# levelshifter.net
KiCad netlist of a schematic drawn in EAGLE
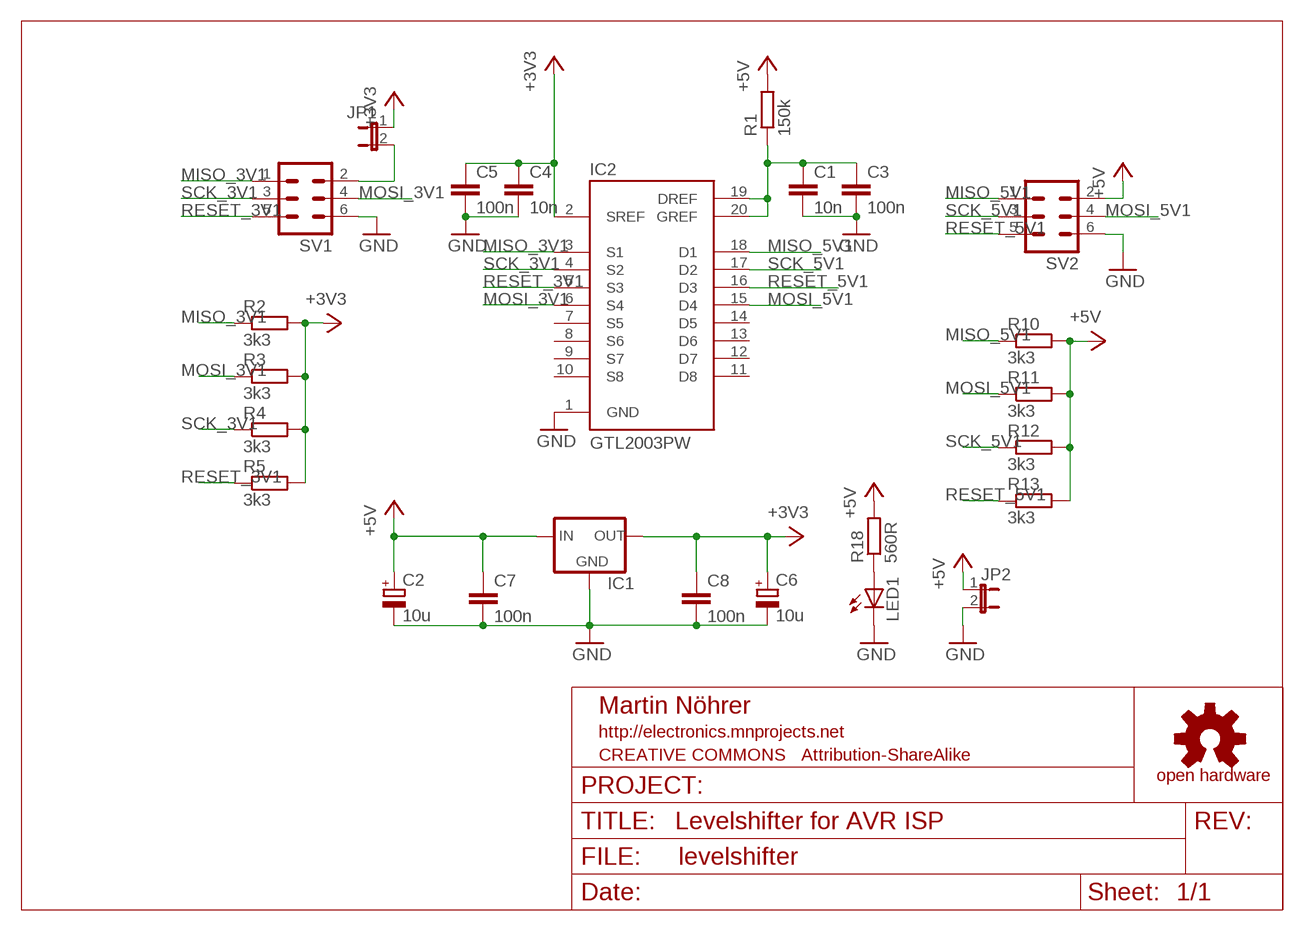
[diagram p0: schematic, sheet 1]

(export (version "E")
  (design (tool "Eeschema 10.0.6"))
  (components
    (comp (ref "C1")
      (value "10n")
      (footprint "eagle-import:C1206")
      (libsource (lib "eagle-import") (part "C-EUC1206"))
    )
    (comp (ref "C2")
      (value "10u")
      (footprint "eagle-import:SMC_C")
      (libsource (lib "eagle-import") (part "CPOL-EUSMCC"))
    )
    (comp (ref "C3")
      (value "100n")
      (footprint "eagle-import:C1206")
      (libsource (lib "eagle-import") (part "C-EUC1206"))
    )
    (comp (ref "C4")
      (value "10n")
      (footprint "eagle-import:C1206")
      (libsource (lib "eagle-import") (part "C-EUC1206"))
    )
    (comp (ref "C5")
      (value "100n")
      (footprint "eagle-import:C1206")
      (libsource (lib "eagle-import") (part "C-EUC1206"))
    )
    (comp (ref "C6")
      (value "10u")
      (footprint "eagle-import:SMC_C")
      (libsource (lib "eagle-import") (part "CPOL-EUSMCC"))
    )
    (comp (ref "C7")
      (value "100n")
      (footprint "eagle-import:C1206")
      (libsource (lib "eagle-import") (part "C-EUC1206"))
    )
    (comp (ref "C8")
      (value "100n")
      (footprint "eagle-import:C1206")
      (libsource (lib "eagle-import") (part "C-EUC1206"))
    )
    (comp (ref "IC1")
      (value "LM1117")
      (footprint "eagle-import:SOT223")
      (libsource (lib "eagle-import") (part "LM1117"))
    )
    (comp (ref "IC2")
      (value "GTL2003PW")
      (footprint "eagle-import:TSSOP20")
      (libsource (lib "eagle-import") (part "GTL2003PW"))
    )
    (comp (ref "JP1")
      (value "JP1E")
      (footprint "eagle-import:JP1")
      (libsource (lib "eagle-import") (part "JP1E"))
    )
    (comp (ref "JP2")
      (value "JP1E")
      (footprint "eagle-import:JP1")
      (libsource (lib "eagle-import") (part "JP1E"))
    )
    (comp (ref "LED1")
      (value "LEDSMT1206")
      (footprint "eagle-import:1206")
      (libsource (lib "eagle-import") (part "LEDSMT1206"))
    )
    (comp (ref "R1")
      (value "150k")
      (footprint "eagle-import:R1206")
      (libsource (lib "eagle-import") (part "R-EU_R1206"))
    )
    (comp (ref "R2")
      (value "3k3")
      (footprint "eagle-import:R1206")
      (libsource (lib "eagle-import") (part "R-EU_R1206"))
    )
    (comp (ref "R3")
      (value "3k3")
      (footprint "eagle-import:R1206")
      (libsource (lib "eagle-import") (part "R-EU_R1206"))
    )
    (comp (ref "R4")
      (value "3k3")
      (footprint "eagle-import:R1206")
      (libsource (lib "eagle-import") (part "R-EU_R1206"))
    )
    (comp (ref "R5")
      (value "3k3")
      (footprint "eagle-import:R1206")
      (libsource (lib "eagle-import") (part "R-EU_R1206"))
    )
    (comp (ref "R10")
      (value "3k3")
      (footprint "eagle-import:R1206")
      (libsource (lib "eagle-import") (part "R-EU_R1206"))
    )
    (comp (ref "R11")
      (value "3k3")
      (footprint "eagle-import:R1206")
      (libsource (lib "eagle-import") (part "R-EU_R1206"))
    )
    (comp (ref "R12")
      (value "3k3")
      (footprint "eagle-import:R1206")
      (libsource (lib "eagle-import") (part "R-EU_R1206"))
    )
    (comp (ref "R13")
      (value "3k3")
      (footprint "eagle-import:R1206")
      (libsource (lib "eagle-import") (part "R-EU_R1206"))
    )
    (comp (ref "R18")
      (value "560R")
      (footprint "eagle-import:R1206")
      (libsource (lib "eagle-import") (part "R-EU_R1206"))
    )
    (comp (ref "SV1")
      (value "ML6")
      (footprint "eagle-import:ML6")
      (libsource (lib "eagle-import") (part "ML6"))
    )
    (comp (ref "SV2")
      (value "ML6")
      (footprint "eagle-import:ML6")
      (libsource (lib "eagle-import") (part "ML6"))
    )
  )
  (nets
    (net (code "1") (name "+3V3") (class "Default")
      (node (ref "C4") (pin "1") (pinfunction "1_1") (pintype "passive"))
      (node (ref "C5") (pin "1") (pinfunction "1_1") (pintype "passive"))
      (node (ref "C6") (pin "+") (pinfunction "+_+") (pintype "passive"))
      (node (ref "C8") (pin "1") (pinfunction "1_1") (pintype "passive"))
      (node (ref "IC1") (pin "2") (pinfunction "OUT_2") (pintype "passive"))
      (node (ref "IC2") (pin "2") (pinfunction "SREF_2") (pintype "bidirectional"))
      (node (ref "JP1") (pin "1") (pinfunction "1_1") (pintype "passive"))
      (node (ref "R2") (pin "2") (pinfunction "2_2") (pintype "passive"))
      (node (ref "R3") (pin "2") (pinfunction "2_2") (pintype "passive"))
      (node (ref "R4") (pin "2") (pinfunction "2_2") (pintype "passive"))
      (node (ref "R5") (pin "2") (pinfunction "2_2") (pintype "passive"))
    )
    (net (code "2") (name "+5V") (class "Default")
      (node (ref "C2") (pin "+") (pinfunction "+_+") (pintype "passive"))
      (node (ref "C7") (pin "1") (pinfunction "1_1") (pintype "passive"))
      (node (ref "IC1") (pin "3") (pinfunction "IN_3") (pintype "input"))
      (node (ref "JP2") (pin "1") (pinfunction "1_1") (pintype "passive"))
      (node (ref "R1") (pin "2") (pinfunction "2_2") (pintype "passive"))
      (node (ref "R10") (pin "2") (pinfunction "2_2") (pintype "passive"))
      (node (ref "R11") (pin "2") (pinfunction "2_2") (pintype "passive"))
      (node (ref "R12") (pin "2") (pinfunction "2_2") (pintype "passive"))
      (node (ref "R13") (pin "2") (pinfunction "2_2") (pintype "passive"))
      (node (ref "R18") (pin "2") (pinfunction "2_2") (pintype "passive"))
      (node (ref "SV2") (pin "2") (pinfunction "2_2") (pintype "passive"))
    )
    (net (code "3") (name "/MISO_3V1") (class "Default")
      (node (ref "IC2") (pin "3") (pinfunction "S1_3") (pintype "bidirectional"))
      (node (ref "R2") (pin "1") (pinfunction "1_1") (pintype "passive"))
      (node (ref "SV1") (pin "1") (pinfunction "1_1") (pintype "passive"))
    )
    (net (code "4") (name "/MISO_5V1") (class "Default")
      (node (ref "IC2") (pin "18") (pinfunction "D1_18") (pintype "bidirectional"))
      (node (ref "R10") (pin "1") (pinfunction "1_1") (pintype "passive"))
      (node (ref "SV2") (pin "1") (pinfunction "1_1") (pintype "passive"))
    )
    (net (code "5") (name "/MOSI_3V1") (class "Default")
      (node (ref "IC2") (pin "6") (pinfunction "S4_6") (pintype "bidirectional"))
      (node (ref "R3") (pin "1") (pinfunction "1_1") (pintype "passive"))
      (node (ref "SV1") (pin "4") (pinfunction "4_4") (pintype "passive"))
    )
    (net (code "6") (name "/MOSI_5V1") (class "Default")
      (node (ref "IC2") (pin "15") (pinfunction "D4_15") (pintype "bidirectional"))
      (node (ref "R11") (pin "1") (pinfunction "1_1") (pintype "passive"))
      (node (ref "SV2") (pin "4") (pinfunction "4_4") (pintype "passive"))
    )
    (net (code "7") (name "/RESET_3V1") (class "Default")
      (node (ref "IC2") (pin "5") (pinfunction "S3_5") (pintype "bidirectional"))
      (node (ref "R5") (pin "1") (pinfunction "1_1") (pintype "passive"))
      (node (ref "SV1") (pin "5") (pinfunction "5_5") (pintype "passive"))
    )
    (net (code "8") (name "/RESET_5V1") (class "Default")
      (node (ref "IC2") (pin "16") (pinfunction "D3_16") (pintype "bidirectional"))
      (node (ref "R13") (pin "1") (pinfunction "1_1") (pintype "passive"))
      (node (ref "SV2") (pin "5") (pinfunction "5_5") (pintype "passive"))
    )
    (net (code "9") (name "/SCK_3V1") (class "Default")
      (node (ref "IC2") (pin "4") (pinfunction "S2_4") (pintype "bidirectional"))
      (node (ref "R4") (pin "1") (pinfunction "1_1") (pintype "passive"))
      (node (ref "SV1") (pin "3") (pinfunction "3_3") (pintype "passive"))
    )
    (net (code "10") (name "/SCK_5V1") (class "Default")
      (node (ref "IC2") (pin "17") (pinfunction "D2_17") (pintype "bidirectional"))
      (node (ref "R12") (pin "1") (pinfunction "1_1") (pintype "passive"))
      (node (ref "SV2") (pin "3") (pinfunction "3_3") (pintype "passive"))
    )
    (net (code "11") (name "GND") (class "Default")
      (node (ref "C1") (pin "2") (pinfunction "2_2") (pintype "passive"))
      (node (ref "C2") (pin "-") (pinfunction "-_-") (pintype "passive"))
      (node (ref "C3") (pin "2") (pinfunction "2_2") (pintype "passive"))
      (node (ref "C4") (pin "2") (pinfunction "2_2") (pintype "passive"))
      (node (ref "C5") (pin "2") (pinfunction "2_2") (pintype "passive"))
      (node (ref "C6") (pin "-") (pinfunction "-_-") (pintype "passive"))
      (node (ref "C7") (pin "2") (pinfunction "2_2") (pintype "passive"))
      (node (ref "C8") (pin "2") (pinfunction "2_2") (pintype "passive"))
      (node (ref "IC1") (pin "1") (pinfunction "GND_1") (pintype "input"))
      (node (ref "IC2") (pin "1") (pinfunction "GND_1") (pintype "bidirectional"))
      (node (ref "JP2") (pin "2") (pinfunction "2_2") (pintype "passive"))
      (node (ref "LED1") (pin "C") (pinfunction "C_C") (pintype "passive"))
      (node (ref "SV1") (pin "6") (pinfunction "6_6") (pintype "passive"))
      (node (ref "SV2") (pin "6") (pinfunction "6_6") (pintype "passive"))
    )
    (net (code "12") (name "Net-(IC2-DREF)") (class "Default")
      (node (ref "C1") (pin "1") (pinfunction "1_1") (pintype "passive"))
      (node (ref "C3") (pin "1") (pinfunction "1_1") (pintype "passive"))
      (node (ref "IC2") (pin "19") (pinfunction "DREF_19") (pintype "bidirectional"))
      (node (ref "IC2") (pin "20") (pinfunction "GREF_20") (pintype "bidirectional"))
      (node (ref "R1") (pin "1") (pinfunction "1_1") (pintype "passive"))
    )
    (net (code "13") (name "Net-(JP1-Pad2)") (class "Default")
      (node (ref "JP1") (pin "2") (pinfunction "2_2") (pintype "passive"))
      (node (ref "SV1") (pin "2") (pinfunction "2_2") (pintype "passive"))
    )
    (net (code "14") (name "Net-(LED1-PadA)") (class "Default")
      (node (ref "LED1") (pin "A") (pinfunction "A_A") (pintype "passive"))
      (node (ref "R18") (pin "1") (pinfunction "1_1") (pintype "passive"))
    )
    (net (code "15") (name "unconnected-(IC2-D5-Pad14)") (class "Default")
      (node (ref "IC2") (pin "14") (pinfunction "D5_14") (pintype "bidirectional"))
    )
    (net (code "16") (name "unconnected-(IC2-D6-Pad13)") (class "Default")
      (node (ref "IC2") (pin "13") (pinfunction "D6_13") (pintype "bidirectional"))
    )
    (net (code "17") (name "unconnected-(IC2-D7-Pad12)") (class "Default")
      (node (ref "IC2") (pin "12") (pinfunction "D7_12") (pintype "bidirectional"))
    )
    (net (code "18") (name "unconnected-(IC2-D8-Pad11)") (class "Default")
      (node (ref "IC2") (pin "11") (pinfunction "D8_11") (pintype "bidirectional"))
    )
    (net (code "19") (name "unconnected-(IC2-S5-Pad7)") (class "Default")
      (node (ref "IC2") (pin "7") (pinfunction "S5_7") (pintype "bidirectional"))
    )
    (net (code "20") (name "unconnected-(IC2-S6-Pad8)") (class "Default")
      (node (ref "IC2") (pin "8") (pinfunction "S6_8") (pintype "bidirectional"))
    )
    (net (code "21") (name "unconnected-(IC2-S7-Pad9)") (class "Default")
      (node (ref "IC2") (pin "9") (pinfunction "S7_9") (pintype "bidirectional"))
    )
    (net (code "22") (name "unconnected-(IC2-S8-Pad10)") (class "Default")
      (node (ref "IC2") (pin "10") (pinfunction "S8_10") (pintype "bidirectional"))
    )
  )
)
